# Matrix_Controller.net
KiCad netlist of a schematic drawn in Altium Designer
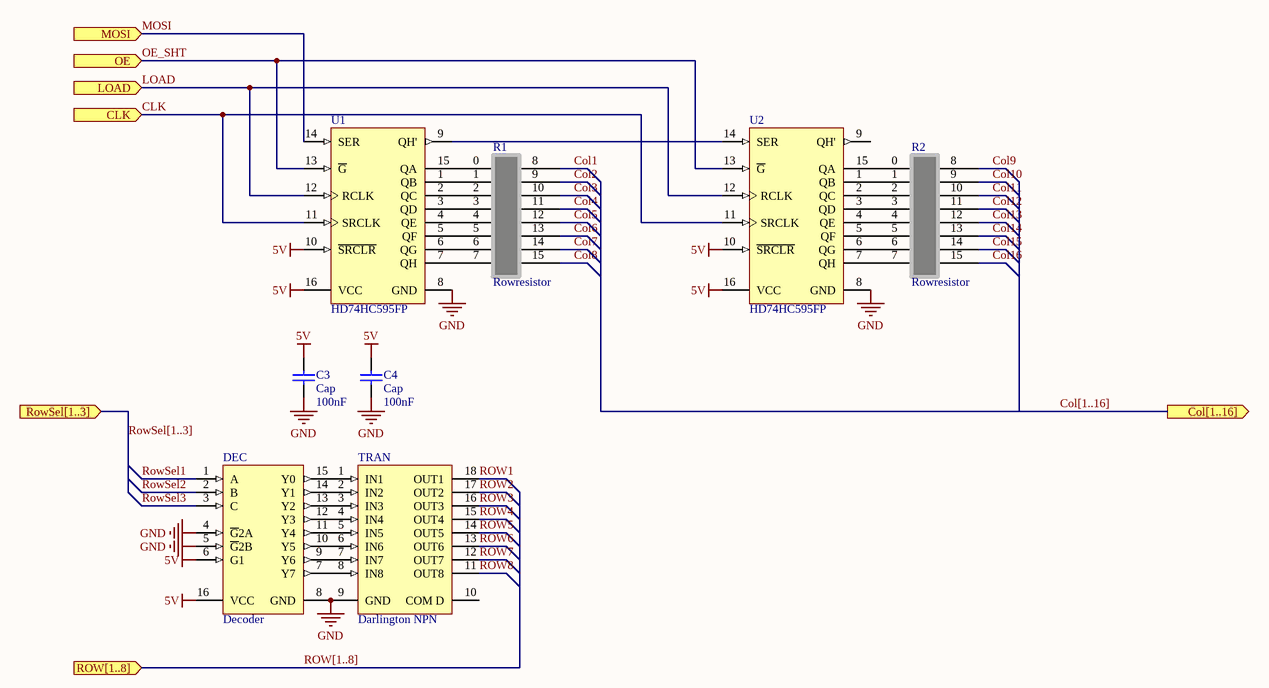
[diagram p0: Matrix_Controller.SchDoc]

(export (version "E")
  (design (tool "Eeschema 10.0.6"))
  (components
    (comp (ref "C3")
      (value "Cap")
      (footprint "6-0805_M")
      (description "Capacitor")
      (fields (field (name "ALTIUM_VALUE") "100nF") (field (name "PUBLISHER") "Altium Limited"))
      (libsource (lib "Miscellaneous Devices") (part "Cap"))
    )
    (comp (ref "C4")
      (value "Cap")
      (footprint "6-0805_M")
      (description "Capacitor")
      (fields (field (name "ALTIUM_VALUE") "100nF") (field (name "PUBLISHER") "Altium Limited"))
      (libsource (lib "Miscellaneous Devices") (part "Cap"))
    )
    (comp (ref "DEC")
      (value "Decoder")
      (footprint "PRSP0016DH-B_N")
      (description "3-to-8 Line Decoder / Demultiplexer")
      (fields (field (name "PUBLISHER") "Altium Limited"))
      (libsource (lib "Renesas Logic") (part "HD74HC238FP"))
    )
    (comp (ref "R1")
      (value "Rowresistor")
      (footprint "Rowres")
      (description "Row resistor, 8")
      (libsource (lib "Rowres") (part "Rowres"))
    )
    (comp (ref "R2")
      (value "Rowresistor")
      (footprint "Rowres")
      (description "Row resistor, 8")
      (libsource (lib "Rowres") (part "Rowres"))
    )
    (comp (ref "TRAN")
      (value "Darlington NPN")
      (footprint "LW18_N")
      (description "High-Voltage, High-Current Darlington Array")
      (fields (field (name "PUBLISHER") "Altium Limited"))
      (libsource (lib "Allegro Interface Darlington Driver") (part "ULN2803LW"))
    )
    (comp (ref "U1")
      (value "HD74HC595FP")
      (footprint "PRSP0016DH-B_N")
      (description "8-bit Shift Register / Latch with 3-State Outputs")
      (fields (field (name "PUBLISHER") "Altium Limited"))
      (libsource (lib "Renesas Logic") (part "HD74HC595FP"))
    )
    (comp (ref "U2")
      (value "HD74HC595FP")
      (footprint "PRSP0016DH-B_N")
      (description "8-bit Shift Register / Latch with 3-State Outputs")
      (fields (field (name "PUBLISHER") "Altium Limited"))
      (libsource (lib "Renesas Logic") (part "HD74HC595FP"))
    )
  )
  (nets
    (net (code "1") (name "/CLK") (class "Default")
      (node (ref "U1") (pin "11") (pinfunction "SRCLK_11") (pintype "input"))
      (node (ref "U2") (pin "11") (pinfunction "SRCLK_11") (pintype "input"))
    )
    (net (code "2") (name "/Col1") (class "Default") (node (ref "R1") (pin "8") (pintype "passive")))
    (net (code "3") (name "/Col2") (class "Default") (node (ref "R1") (pin "9") (pintype "passive")))
    (net (code "4") (name "/Col3") (class "Default") (node (ref "R1") (pin "10") (pintype "passive")))
    (net (code "5") (name "/Col4") (class "Default") (node (ref "R1") (pin "11") (pintype "passive")))
    (net (code "6") (name "/Col5") (class "Default") (node (ref "R1") (pin "12") (pintype "passive")))
    (net (code "7") (name "/Col6") (class "Default") (node (ref "R1") (pin "13") (pintype "passive")))
    (net (code "8") (name "/Col7") (class "Default") (node (ref "R1") (pin "14") (pintype "passive")))
    (net (code "9") (name "/Col8") (class "Default") (node (ref "R1") (pin "15") (pintype "passive")))
    (net (code "10") (name "/Col9") (class "Default") (node (ref "R2") (pin "8") (pintype "passive")))
    (net (code "11") (name "/Col10") (class "Default") (node (ref "R2") (pin "9") (pintype "passive")))
    (net (code "12") (name "/Col11") (class "Default") (node (ref "R2") (pin "10") (pintype "passive")))
    (net (code "13") (name "/Col12") (class "Default") (node (ref "R2") (pin "11") (pintype "passive")))
    (net (code "14") (name "/Col13") (class "Default") (node (ref "R2") (pin "12") (pintype "passive")))
    (net (code "15") (name "/Col14") (class "Default") (node (ref "R2") (pin "13") (pintype "passive")))
    (net (code "16") (name "/Col15") (class "Default") (node (ref "R2") (pin "14") (pintype "passive")))
    (net (code "17") (name "/Col16") (class "Default") (node (ref "R2") (pin "15") (pintype "passive")))
    (net (code "19") (name "/LOAD") (class "Default")
      (node (ref "U1") (pin "12") (pinfunction "RCLK_12") (pintype "input"))
      (node (ref "U2") (pin "12") (pinfunction "RCLK_12") (pintype "input"))
    )
    (net (code "20") (name "/MOSI") (class "Default")
      (node (ref "U1") (pin "14") (pinfunction "SER_14") (pintype "input"))
    )
    (net (code "21") (name "/OE_SHT") (class "Default")
      (node (ref "U1") (pin "13") (pinfunction "~{G}_13") (pintype "input"))
      (node (ref "U2") (pin "13") (pinfunction "~{G}_13") (pintype "input"))
    )
    (net (code "22") (name "/ROW1") (class "Default")
      (node (ref "TRAN") (pin "18") (pinfunction "OUT1_18") (pintype "open_collector"))
    )
    (net (code "23") (name "/ROW2") (class "Default")
      (node (ref "TRAN") (pin "17") (pinfunction "OUT2_17") (pintype "open_collector"))
    )
    (net (code "24") (name "/ROW3") (class "Default")
      (node (ref "TRAN") (pin "16") (pinfunction "OUT3_16") (pintype "open_collector"))
    )
    (net (code "25") (name "/ROW4") (class "Default")
      (node (ref "TRAN") (pin "15") (pinfunction "OUT4_15") (pintype "open_collector"))
    )
    (net (code "26") (name "/ROW5") (class "Default")
      (node (ref "TRAN") (pin "14") (pinfunction "OUT5_14") (pintype "open_collector"))
    )
    (net (code "27") (name "/ROW6") (class "Default")
      (node (ref "TRAN") (pin "13") (pinfunction "OUT6_13") (pintype "open_collector"))
    )
    (net (code "28") (name "/ROW7") (class "Default")
      (node (ref "TRAN") (pin "12") (pinfunction "OUT7_12") (pintype "open_collector"))
    )
    (net (code "29") (name "/ROW8") (class "Default")
      (node (ref "TRAN") (pin "11") (pinfunction "OUT8_11") (pintype "open_collector"))
    )
    (net (code "31") (name "/RowSel1") (class "Default")
      (node (ref "DEC") (pin "1") (pinfunction "A_1") (pintype "input"))
    )
    (net (code "32") (name "/RowSel2") (class "Default")
      (node (ref "DEC") (pin "2") (pinfunction "B_2") (pintype "input"))
    )
    (net (code "33") (name "/RowSel3") (class "Default")
      (node (ref "DEC") (pin "3") (pinfunction "C_3") (pintype "input"))
    )
    (net (code "35") (name "5V") (class "Default")
      (node (ref "C3") (pin "1") (pinfunction "1_1") (pintype "passive"))
      (node (ref "C4") (pin "1") (pinfunction "1_1") (pintype "passive"))
      (node (ref "DEC") (pin "16") (pinfunction "VCC_16") (pintype "power_in"))
      (node (ref "DEC") (pin "6") (pinfunction "G1_6") (pintype "input"))
      (node (ref "U1") (pin "10") (pinfunction "~{SRCLR}_10") (pintype "input"))
      (node (ref "U1") (pin "16") (pinfunction "VCC_16") (pintype "power_in"))
      (node (ref "U2") (pin "10") (pinfunction "~{SRCLR}_10") (pintype "input"))
      (node (ref "U2") (pin "16") (pinfunction "VCC_16") (pintype "power_in"))
    )
    (net (code "36") (name "GND") (class "Default")
      (node (ref "C3") (pin "2") (pinfunction "2_2") (pintype "passive"))
      (node (ref "C4") (pin "2") (pinfunction "2_2") (pintype "passive"))
      (node (ref "DEC") (pin "4") (pinfunction "~{G}2A_4") (pintype "input"))
      (node (ref "DEC") (pin "5") (pinfunction "~{G}2B_5") (pintype "input"))
      (node (ref "DEC") (pin "8") (pinfunction "GND_8") (pintype "power_in"))
      (node (ref "TRAN") (pin "9") (pinfunction "GND_9") (pintype "power_in"))
      (node (ref "U1") (pin "8") (pinfunction "GND_8") (pintype "power_in"))
      (node (ref "U2") (pin "8") (pinfunction "GND_8") (pintype "power_in"))
    )
    (net (code "37") (name "Net-(DEC-Y0)") (class "Default")
      (node (ref "DEC") (pin "15") (pinfunction "Y0_15") (pintype "output"))
      (node (ref "TRAN") (pin "1") (pinfunction "IN1_1") (pintype "input"))
    )
    (net (code "38") (name "Net-(DEC-Y1)") (class "Default")
      (node (ref "DEC") (pin "14") (pinfunction "Y1_14") (pintype "output"))
      (node (ref "TRAN") (pin "2") (pinfunction "IN2_2") (pintype "input"))
    )
    (net (code "39") (name "Net-(DEC-Y2)") (class "Default")
      (node (ref "DEC") (pin "13") (pinfunction "Y2_13") (pintype "output"))
      (node (ref "TRAN") (pin "3") (pinfunction "IN3_3") (pintype "input"))
    )
    (net (code "40") (name "Net-(DEC-Y3)") (class "Default")
      (node (ref "DEC") (pin "12") (pinfunction "Y3_12") (pintype "output"))
      (node (ref "TRAN") (pin "4") (pinfunction "IN4_4") (pintype "input"))
    )
    (net (code "41") (name "Net-(DEC-Y4)") (class "Default")
      (node (ref "DEC") (pin "11") (pinfunction "Y4_11") (pintype "output"))
      (node (ref "TRAN") (pin "5") (pinfunction "IN5_5") (pintype "input"))
    )
    (net (code "42") (name "Net-(DEC-Y5)") (class "Default")
      (node (ref "DEC") (pin "10") (pinfunction "Y5_10") (pintype "output"))
      (node (ref "TRAN") (pin "6") (pinfunction "IN6_6") (pintype "input"))
    )
    (net (code "43") (name "Net-(DEC-Y6)") (class "Default")
      (node (ref "DEC") (pin "9") (pinfunction "Y6_9") (pintype "output"))
      (node (ref "TRAN") (pin "7") (pinfunction "IN7_7") (pintype "input"))
    )
    (net (code "44") (name "Net-(DEC-Y7)") (class "Default")
      (node (ref "DEC") (pin "7") (pinfunction "Y7_7") (pintype "output"))
      (node (ref "TRAN") (pin "8") (pinfunction "IN8_8") (pintype "input"))
    )
    (net (code "45") (name "Net-(U1-QA)") (class "Default")
      (node (ref "R1") (pin "0") (pintype "passive"))
      (node (ref "U1") (pin "15") (pinfunction "QA_15") (pintype "tri_state"))
    )
    (net (code "46") (name "Net-(U1-QB)") (class "Default")
      (node (ref "R1") (pin "1") (pintype "passive"))
      (node (ref "U1") (pin "1") (pinfunction "QB_1") (pintype "tri_state"))
    )
    (net (code "47") (name "Net-(U1-QC)") (class "Default")
      (node (ref "R1") (pin "2") (pintype "passive"))
      (node (ref "U1") (pin "2") (pinfunction "QC_2") (pintype "tri_state"))
    )
    (net (code "48") (name "Net-(U1-QD)") (class "Default")
      (node (ref "R1") (pin "3") (pintype "passive"))
      (node (ref "U1") (pin "3") (pinfunction "QD_3") (pintype "tri_state"))
    )
    (net (code "49") (name "Net-(U1-QE)") (class "Default")
      (node (ref "R1") (pin "4") (pintype "passive"))
      (node (ref "U1") (pin "4") (pinfunction "QE_4") (pintype "tri_state"))
    )
    (net (code "50") (name "Net-(U1-QF)") (class "Default")
      (node (ref "R1") (pin "5") (pintype "passive"))
      (node (ref "U1") (pin "5") (pinfunction "QF_5") (pintype "tri_state"))
    )
    (net (code "51") (name "Net-(U1-QG)") (class "Default")
      (node (ref "R1") (pin "6") (pintype "passive"))
      (node (ref "U1") (pin "6") (pinfunction "QG_6") (pintype "tri_state"))
    )
    (net (code "52") (name "Net-(U1-QH')") (class "Default")
      (node (ref "U1") (pin "9") (pinfunction "QH'_9") (pintype "output"))
      (node (ref "U2") (pin "14") (pinfunction "SER_14") (pintype "input"))
    )
    (net (code "53") (name "Net-(U1-QH)") (class "Default")
      (node (ref "R1") (pin "7") (pintype "passive"))
      (node (ref "U1") (pin "7") (pinfunction "QH_7") (pintype "tri_state"))
    )
    (net (code "54") (name "Net-(U2-QA)") (class "Default")
      (node (ref "R2") (pin "0") (pintype "passive"))
      (node (ref "U2") (pin "15") (pinfunction "QA_15") (pintype "tri_state"))
    )
    (net (code "55") (name "Net-(U2-QB)") (class "Default")
      (node (ref "R2") (pin "1") (pintype "passive"))
      (node (ref "U2") (pin "1") (pinfunction "QB_1") (pintype "tri_state"))
    )
    (net (code "56") (name "Net-(U2-QC)") (class "Default")
      (node (ref "R2") (pin "2") (pintype "passive"))
      (node (ref "U2") (pin "2") (pinfunction "QC_2") (pintype "tri_state"))
    )
    (net (code "57") (name "Net-(U2-QD)") (class "Default")
      (node (ref "R2") (pin "3") (pintype "passive"))
      (node (ref "U2") (pin "3") (pinfunction "QD_3") (pintype "tri_state"))
    )
    (net (code "58") (name "Net-(U2-QE)") (class "Default")
      (node (ref "R2") (pin "4") (pintype "passive"))
      (node (ref "U2") (pin "4") (pinfunction "QE_4") (pintype "tri_state"))
    )
    (net (code "59") (name "Net-(U2-QF)") (class "Default")
      (node (ref "R2") (pin "5") (pintype "passive"))
      (node (ref "U2") (pin "5") (pinfunction "QF_5") (pintype "tri_state"))
    )
    (net (code "60") (name "Net-(U2-QG)") (class "Default")
      (node (ref "R2") (pin "6") (pintype "passive"))
      (node (ref "U2") (pin "6") (pinfunction "QG_6") (pintype "tri_state"))
    )
    (net (code "61") (name "Net-(U2-QH)") (class "Default")
      (node (ref "R2") (pin "7") (pintype "passive"))
      (node (ref "U2") (pin "7") (pinfunction "QH_7") (pintype "tri_state"))
    )
    (net (code "62") (name "unconnected-(TRAN-COM_D-Pad10)") (class "Default")
      (node (ref "TRAN") (pin "10") (pinfunction "COM_D_10") (pintype "passive"))
    )
    (net (code "63") (name "unconnected-(U2-QH'-Pad9)") (class "Default")
      (node (ref "U2") (pin "9") (pinfunction "QH'_9") (pintype "output"))
    )
  )
)
